# 4_-INTERFACE_BOARD.net
KiCad netlist of a schematic drawn in Altium Designer
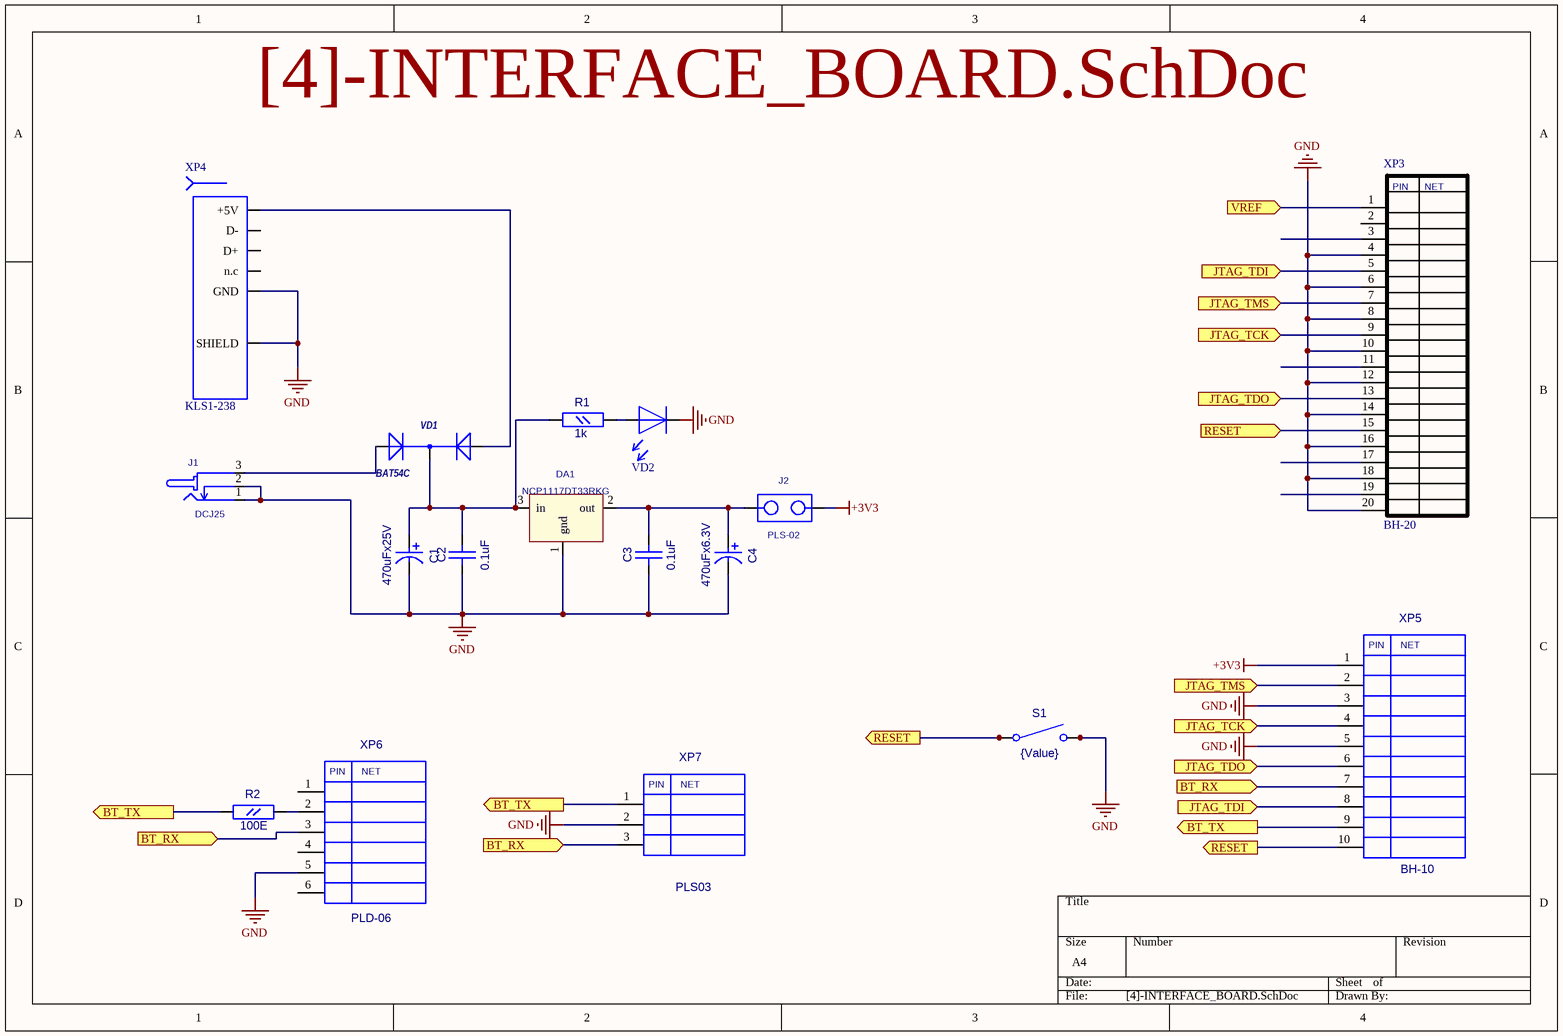
[diagram p0: [4]-INTERFACE_BOARD.SchDoc]

(export (version "E")
  (design (tool "Eeschema 10.0.6"))
  (components
    (comp (ref "C1")
      (value "470uFx25V")
      (footprint "CC8X3.5")
      (description "CAP0.35")
      (libsource (lib "fizik_lib") (part "CAP0.35"))
    )
    (comp (ref "C2")
      (value "0.1uF")
      (footprint "CC0603")
      (description "CC0603")
      (libsource (lib "fizik_lib") (part "CC0603"))
    )
    (comp (ref "C3")
      (value "0.1uF")
      (footprint "CC0603")
      (description "CC0603")
      (libsource (lib "fizik_lib") (part "CC0603"))
    )
    (comp (ref "C4")
      (value "470uFx6.3V")
      (footprint "CC8X3.5")
      (description "CAP0.35")
      (libsource (lib "fizik_lib") (part "CAP0.35"))
    )
    (comp (ref "DA1")
      (value "NCP1117DT33RKG")
      (footprint "D-PAK(TO-252AA)")
      (description "Linear Regulator 3.3V")
      (libsource (lib "fizik_lib") (part "NCP1117DT33RKG"))
    )
    (comp (ref "J1") (value "DCJ25") (footprint "DCJ25") (libsource (lib "fizik_lib") (part "DCJ25")))
    (comp (ref "J2") (value "PLS-02") (footprint "PLS-02") (libsource (lib "fizik_lib") (part "PLS-02")))
    (comp (ref "R1")
      (value "1k")
      (footprint "RC0603")
      (description "RC0603")
      (libsource (lib "fizik_lib") (part "RC0603"))
    )
    (comp (ref "R2")
      (value "100E")
      (footprint "RC0603")
      (description "RC0603")
      (libsource (lib "gprs_modem_2") (part "RC0603"))
    )
    (comp (ref "S1")
      (value "{Value}")
      (footprint "7906H-1")
      (description "Switch, Single Pole, Single Throw, Normally Open")
      (fields (field (name "Comment") "SWT-2/5"))
      (libsource (lib "fizik_lib") (part "SWT-2/5"))
    )
    (comp (ref "VD1")
      (value "BAT54C")
      (footprint "SOT-23(123)")
      (libsource (lib "fizik_lib") (part "BAT54C"))
    )
    (comp (ref "VD2")
      (value "LED_0805")
      (footprint "LED0805")
      (libsource (lib "fizik_lib") (part "LED_0805"))
    )
    (comp (ref "XP3") (value "BH-20") (footprint "BH-20") (libsource (lib "fizik_lib") (part "BH-20")))
    (comp (ref "XP4")
      (value "KLS1-238")
      (footprint "KLS1-238")
      (libsource (lib "fizik_lib") (part "MicroUSB KLS1-238"))
    )
    (comp (ref "XP5") (value "BH-10") (footprint "BH-10") (libsource (lib "fizik_lib") (part "BH-10")))
    (comp (ref "XP6")
      (value "PLD-06")
      (footprint "PIN6")
      (description "PLD06")
      (libsource (lib "gprs_modem") (part "PLD-06"))
    )
    (comp (ref "XP7") (value "PLS03") (footprint "PLS-03") (libsource (lib "fizik_lib") (part "PLS03")))
  )
  (nets
    (net (code "1") (name "+3V3") (class "Default")
      (node (ref "J2") (pin "2") (pintype "passive"))
      (node (ref "XP5") (pin "1") (pinfunction "1_1") (pintype "passive"))
    )
    (net (code "2") (name "/BT_RX") (class "Default")
      (node (ref "XP5") (pin "7") (pinfunction "7_7") (pintype "passive"))
      (node (ref "XP6") (pin "3") (pinfunction "3_3") (pintype "passive"))
      (node (ref "XP7") (pin "3") (pinfunction "3_3") (pintype "passive"))
    )
    (net (code "3") (name "/BT_TX") (class "Default")
      (node (ref "R2") (pin "1") (pinfunction "A_1") (pintype "passive"))
      (node (ref "XP5") (pin "9") (pinfunction "9_9") (pintype "passive"))
      (node (ref "XP7") (pin "1") (pinfunction "1_1") (pintype "passive"))
    )
    (net (code "4") (name "/JTAG_TCK") (class "Default")
      (node (ref "XP3") (pin "9") (pinfunction "9_9") (pintype "passive"))
      (node (ref "XP5") (pin "4") (pinfunction "4_4") (pintype "passive"))
    )
    (net (code "5") (name "/JTAG_TDI") (class "Default")
      (node (ref "XP3") (pin "5") (pinfunction "5_5") (pintype "passive"))
      (node (ref "XP5") (pin "8") (pinfunction "8_8") (pintype "passive"))
    )
    (net (code "6") (name "/JTAG_TDO") (class "Default")
      (node (ref "XP3") (pin "13") (pinfunction "13_13") (pintype "passive"))
      (node (ref "XP5") (pin "6") (pinfunction "6_6") (pintype "passive"))
    )
    (net (code "7") (name "/JTAG_TMS") (class "Default")
      (node (ref "XP3") (pin "7") (pinfunction "7_7") (pintype "passive"))
      (node (ref "XP5") (pin "2") (pinfunction "2_2") (pintype "passive"))
    )
    (net (code "8") (name "/RESET") (class "Default")
      (node (ref "S1") (pin "1") (pinfunction "C1_1") (pintype "passive"))
      (node (ref "S1") (pin "2") (pintype "passive"))
      (node (ref "XP3") (pin "15") (pinfunction "15_15") (pintype "passive"))
      (node (ref "XP5") (pin "10") (pinfunction "10_10") (pintype "passive"))
    )
    (net (code "9") (name "/VREF") (class "Default")
      (node (ref "XP3") (pin "1") (pinfunction "1_1") (pintype "passive"))
    )
    (net (code "10") (name "GND") (class "Default")
      (node (ref "C1") (pin "2") (pintype "passive"))
      (node (ref "C2") (pin "1") (pinfunction "A_1") (pintype "passive"))
      (node (ref "C3") (pin "1") (pinfunction "A_1") (pintype "passive"))
      (node (ref "C4") (pin "2") (pintype "passive"))
      (node (ref "DA1") (pin "1") (pinfunction "gnd_1") (pintype "passive"))
      (node (ref "J1") (pin "1") (pintype "passive"))
      (node (ref "J1") (pin "2") (pintype "passive"))
      (node (ref "S1") (pin "3") (pinfunction "C2_3") (pintype "passive"))
      (node (ref "S1") (pin "4") (pintype "passive"))
      (node (ref "VD2") (pin "2") (pintype "passive"))
      (node (ref "XP3") (pin "10") (pinfunction "10_10") (pintype "passive"))
      (node (ref "XP3") (pin "12") (pinfunction "12_12") (pintype "passive"))
      (node (ref "XP3") (pin "14") (pinfunction "14_14") (pintype "passive"))
      (node (ref "XP3") (pin "16") (pinfunction "16_16") (pintype "passive"))
      (node (ref "XP3") (pin "18") (pinfunction "16_18") (pintype "passive"))
      (node (ref "XP3") (pin "20") (pinfunction "16_20") (pintype "passive"))
      (node (ref "XP3") (pin "4") (pinfunction "4_4") (pintype "passive"))
      (node (ref "XP3") (pin "6") (pinfunction "6_6") (pintype "passive"))
      (node (ref "XP3") (pin "8") (pinfunction "8_8") (pintype "passive"))
      (node (ref "XP4") (pin "5") (pinfunction "GND_5") (pintype "passive"))
      (node (ref "XP4") (pin "6") (pinfunction "SHIELD_6") (pintype "passive"))
      (node (ref "XP5") (pin "3") (pinfunction "3_3") (pintype "passive"))
      (node (ref "XP5") (pin "5") (pinfunction "5_5") (pintype "passive"))
      (node (ref "XP6") (pin "5") (pinfunction "5_5") (pintype "passive"))
      (node (ref "XP7") (pin "2") (pinfunction "2_2") (pintype "passive"))
    )
    (net (code "11") (name "Net-(C2-B)") (class "Default")
      (node (ref "C1") (pin "1") (pintype "passive"))
      (node (ref "C2") (pin "2") (pinfunction "B_2") (pintype "passive"))
      (node (ref "DA1") (pin "3") (pinfunction "in_3") (pintype "passive"))
      (node (ref "R1") (pin "2") (pinfunction "B_2") (pintype "passive"))
      (node (ref "VD1") (pin "3") (pinfunction "K_3") (pintype "passive"))
    )
    (net (code "12") (name "Net-(C3-B)") (class "Default")
      (node (ref "C3") (pin "2") (pinfunction "B_2") (pintype "passive"))
      (node (ref "C4") (pin "1") (pintype "passive"))
      (node (ref "DA1") (pin "2") (pinfunction "out_2") (pintype "passive"))
      (node (ref "J2") (pin "1") (pintype "passive"))
    )
    (net (code "13") (name "Net-(J1-Pad3)") (class "Default")
      (node (ref "J1") (pin "3") (pintype "passive"))
      (node (ref "VD1") (pin "1") (pinfunction "A_1") (pintype "passive"))
    )
    (net (code "14") (name "Net-(R1-A)") (class "Default")
      (node (ref "R1") (pin "1") (pinfunction "A_1") (pintype "passive"))
      (node (ref "VD2") (pin "1") (pintype "passive"))
    )
    (net (code "15") (name "Net-(R2-B)") (class "Default")
      (node (ref "R2") (pin "2") (pinfunction "B_2") (pintype "passive"))
      (node (ref "XP6") (pin "2") (pinfunction "2_2") (pintype "passive"))
    )
    (net (code "16") (name "Net-(XP4-+5V)") (class "Default")
      (node (ref "VD1") (pin "2") (pinfunction "A_2") (pintype "passive"))
      (node (ref "XP4") (pin "1") (pinfunction "+5V_1") (pintype "passive"))
    )
    (net (code "17") (name "unconnected-(XP3-16-Pad17)") (class "Default")
      (node (ref "XP3") (pin "17") (pinfunction "16_17") (pintype "passive"))
    )
    (net (code "18") (name "unconnected-(XP3-16-Pad19)") (class "Default")
      (node (ref "XP3") (pin "19") (pinfunction "16_19") (pintype "passive"))
    )
    (net (code "19") (name "unconnected-(XP3-Pad2)") (class "Default")
      (node (ref "XP3") (pin "2") (pinfunction "2_2") (pintype "passive"))
    )
    (net (code "20") (name "unconnected-(XP3-Pad3)") (class "Default")
      (node (ref "XP3") (pin "3") (pinfunction "3_3") (pintype "passive"))
    )
    (net (code "21") (name "unconnected-(XP3-Pad11)") (class "Default")
      (node (ref "XP3") (pin "11") (pinfunction "11_11") (pintype "passive"))
    )
    (net (code "22") (name "unconnected-(XP4-D+-Pad3)") (class "Default")
      (node (ref "XP4") (pin "3") (pinfunction "D+_3") (pintype "passive"))
    )
    (net (code "23") (name "unconnected-(XP4-D--Pad2)") (class "Default")
      (node (ref "XP4") (pin "2") (pinfunction "D-_2") (pintype "passive"))
    )
    (net (code "24") (name "unconnected-(XP4-n.c-Pad4)") (class "Default")
      (node (ref "XP4") (pin "4") (pinfunction "n.c_4") (pintype "passive"))
    )
    (net (code "25") (name "unconnected-(XP6-Pad1)") (class "Default")
      (node (ref "XP6") (pin "1") (pinfunction "1_1") (pintype "passive"))
    )
    (net (code "26") (name "unconnected-(XP6-Pad4)") (class "Default")
      (node (ref "XP6") (pin "4") (pinfunction "4_4") (pintype "passive"))
    )
    (net (code "27") (name "unconnected-(XP6-Pad6)") (class "Default")
      (node (ref "XP6") (pin "6") (pinfunction "6_6") (pintype "passive"))
    )
  )
)
